# segnalazione_acustico_luminosa.net
KiCad netlist of a schematic drawn in EAGLE
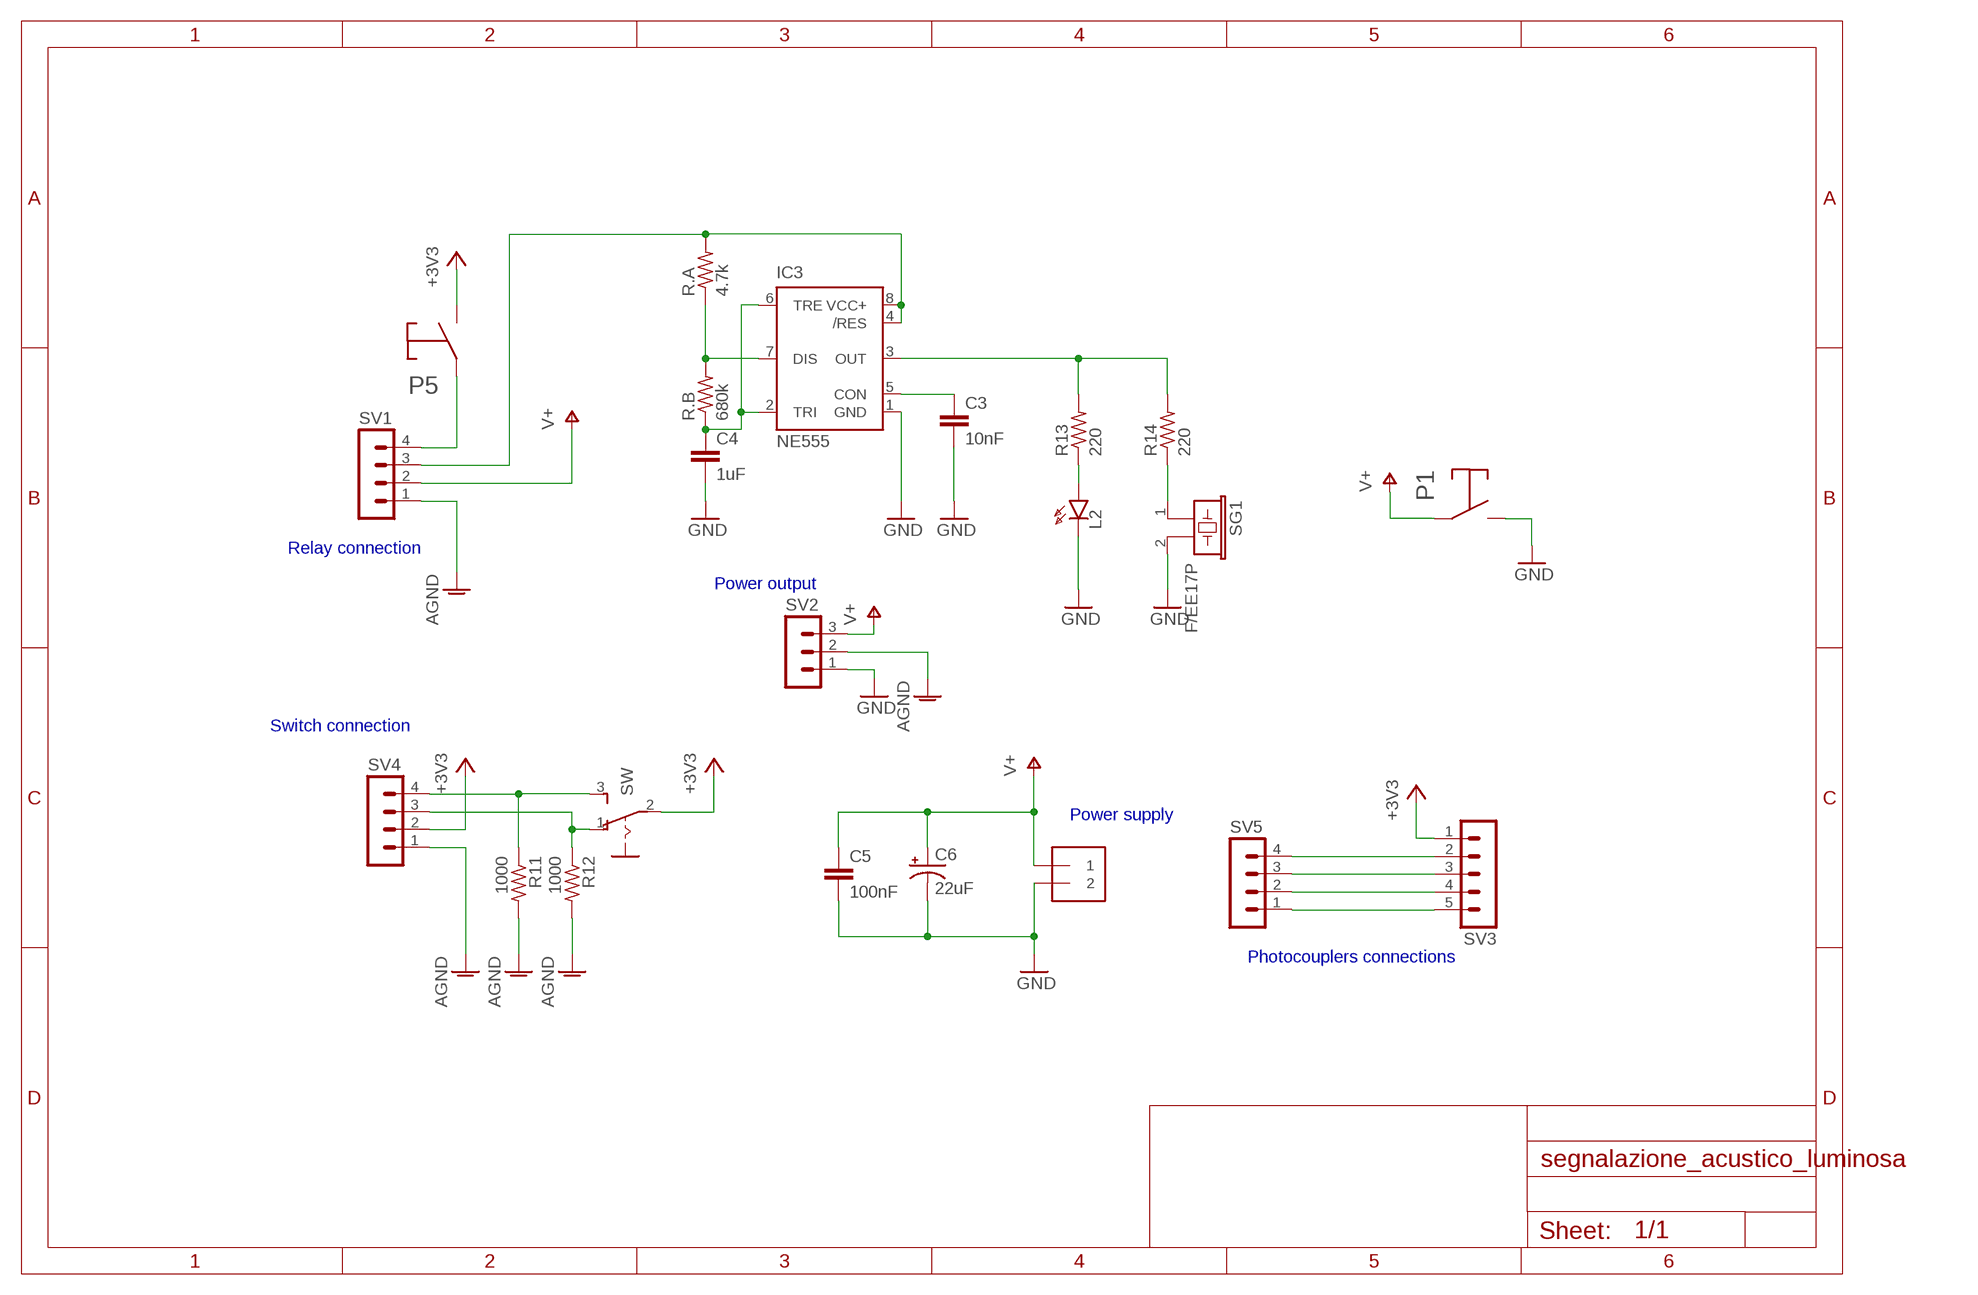
[diagram p0: schematic, sheet 1]

(export (version "E")
  (design (tool "Eeschema 10.0.6"))
  (components
    (comp (ref "C3")
      (value "10nF")
      (footprint "eagle-import:C025-024X044")
      (libsource (lib "eagle-import") (part "C-EU025-024X044"))
    )
    (comp (ref "C4")
      (value "1uF")
      (footprint "eagle-import:C025-024X044")
      (libsource (lib "eagle-import") (part "C-EU025-024X044"))
    )
    (comp (ref "C5")
      (value "100nF")
      (footprint "eagle-import:C025-024X044")
      (libsource (lib "eagle-import") (part "C-EU025-024X044"))
    )
    (comp (ref "C6")
      (value "22uF")
      (footprint "eagle-import:E2,5-6E")
      (libsource (lib "eagle-import") (part "CPOL-USE2,5-6E"))
    )
    (comp (ref "IC3")
      (value "NE555")
      (footprint "eagle-import:DIL-08")
      (fields (field (name "MF") "Arrow Electronics") (field (name "MPN") "NE555N"))
      (libsource (lib "eagle-import") (part "NE555"))
    )
    (comp (ref "J1")
      (value "1X2-3.5MM")
      (footprint "eagle-import:1X2-3.5MM")
      (libsource (lib "eagle-import") (part "1X2-3.5MM"))
    )
    (comp (ref "L2")
      (value "HLMP6")
      (footprint "eagle-import:HLMP6")
      (fields (field (name "MF") "AGILENT TECHNOLOGIES") (field (name "MPN") "HLMP-6500"))
      (libsource (lib "eagle-import") (part "HLMP6"))
    )
    (comp (ref "P1")
      (value "PULS")
      (footprint "eagle-import:2TULIP")
      (libsource (lib "eagle-import") (part "PULS"))
    )
    (comp (ref "P5")
      (value "PULS")
      (footprint "eagle-import:2TULIP")
      (libsource (lib "eagle-import") (part "PULS"))
    )
    (comp (ref "R.A")
      (value "4.7k")
      (footprint "eagle-import:0207_10")
      (libsource (lib "eagle-import") (part "R-US_0207/10"))
    )
    (comp (ref "R.B")
      (value "680k")
      (footprint "eagle-import:0207_10")
      (libsource (lib "eagle-import") (part "R-US_0207/10"))
    )
    (comp (ref "R11")
      (value "1000")
      (footprint "eagle-import:0207_10")
      (libsource (lib "eagle-import") (part "R-US_0207/10"))
    )
    (comp (ref "R12")
      (value "1000")
      (footprint "eagle-import:0207_10")
      (libsource (lib "eagle-import") (part "R-US_0207/10"))
    )
    (comp (ref "R13")
      (value "220")
      (footprint "eagle-import:0207_10")
      (libsource (lib "eagle-import") (part "R-US_0207/10"))
    )
    (comp (ref "R14")
      (value "220")
      (footprint "eagle-import:0207_10")
      (libsource (lib "eagle-import") (part "R-US_0207/10"))
    )
    (comp (ref "SG1")
      (value "F/EE17P")
      (footprint "eagle-import:F_EE17P")
      (libsource (lib "eagle-import") (part "F/EE17P"))
    )
    (comp (ref "SV1")
      (value "MA04-1")
      (footprint "eagle-import:MA04-1")
      (libsource (lib "eagle-import") (part "MA04-1"))
    )
    (comp (ref "SV2")
      (value "MA03-1")
      (footprint "eagle-import:MA03-1")
      (libsource (lib "eagle-import") (part "MA03-1"))
    )
    (comp (ref "SV3")
      (value "MA05-1")
      (footprint "eagle-import:MA05-1")
      (libsource (lib "eagle-import") (part "MA05-1"))
    )
    (comp (ref "SV4")
      (value "MA04-1")
      (footprint "eagle-import:MA04-1")
      (libsource (lib "eagle-import") (part "MA04-1"))
    )
    (comp (ref "SV5")
      (value "MA04-1")
      (footprint "eagle-import:MA04-1")
      (libsource (lib "eagle-import") (part "MA04-1"))
    )
    (comp (ref "SW")
      (value "M251")
      (footprint "eagle-import:M251")
      (libsource (lib "eagle-import") (part "M251"))
    )
  )
  (nets
    (net (code "1") (name "+3V3") (class "Default")
      (node (ref "P5") (pin "1") (pinfunction "P$1_1") (pintype "bidirectional"))
      (node (ref "SV3") (pin "1") (pinfunction "1_1") (pintype "passive"))
      (node (ref "SV4") (pin "2") (pinfunction "2_2") (pintype "passive"))
      (node (ref "SW") (pin "2") (pinfunction "P_2") (pintype "passive"))
    )
    (net (code "2") (name "AGND") (class "Default")
      (node (ref "R11") (pin "2") (pinfunction "2_2") (pintype "passive"))
      (node (ref "R12") (pin "2") (pinfunction "2_2") (pintype "passive"))
      (node (ref "SV1") (pin "1") (pinfunction "1_1") (pintype "passive"))
      (node (ref "SV2") (pin "2") (pinfunction "2_2") (pintype "passive"))
      (node (ref "SV4") (pin "1") (pinfunction "1_1") (pintype "passive"))
    )
    (net (code "3") (name "GND") (class "Default")
      (node (ref "C3") (pin "2") (pinfunction "2_2") (pintype "passive"))
      (node (ref "C4") (pin "2") (pinfunction "2_2") (pintype "passive"))
      (node (ref "C5") (pin "2") (pinfunction "2_2") (pintype "passive"))
      (node (ref "C6") (pin "-") (pinfunction "-_-") (pintype "passive"))
      (node (ref "IC3") (pin "1") (pinfunction "GND_1") (pintype "power_in"))
      (node (ref "J1") (pin "2") (pinfunction "2_2") (pintype "passive"))
      (node (ref "L2") (pin "K") (pinfunction "K_K") (pintype "passive"))
      (node (ref "P1") (pin "1") (pinfunction "P$1_1") (pintype "bidirectional"))
      (node (ref "SG1") (pin "2") (pinfunction "2_2") (pintype "passive"))
      (node (ref "SV2") (pin "1") (pinfunction "1_1") (pintype "passive"))
    )
    (net (code "4") (name "Net-(IC3-CON)") (class "Default")
      (node (ref "C3") (pin "1") (pinfunction "1_1") (pintype "passive"))
      (node (ref "IC3") (pin "5") (pinfunction "CON_5") (pintype "input"))
    )
    (net (code "5") (name "Net-(IC3-DIS)") (class "Default")
      (node (ref "IC3") (pin "7") (pinfunction "DIS_7") (pintype "input"))
      (node (ref "R.A") (pin "1") (pinfunction "1_1") (pintype "passive"))
      (node (ref "R.B") (pin "2") (pinfunction "2_2") (pintype "passive"))
    )
    (net (code "6") (name "Net-(IC3-OUT)") (class "Default")
      (node (ref "IC3") (pin "3") (pinfunction "OUT_3") (pintype "output"))
      (node (ref "R13") (pin "2") (pinfunction "2_2") (pintype "passive"))
      (node (ref "R14") (pin "2") (pinfunction "2_2") (pintype "passive"))
    )
    (net (code "7") (name "Net-(IC3-TRE)") (class "Default")
      (node (ref "C4") (pin "1") (pinfunction "1_1") (pintype "passive"))
      (node (ref "IC3") (pin "2") (pinfunction "TRI_2") (pintype "input"))
      (node (ref "IC3") (pin "6") (pinfunction "TRE_6") (pintype "input"))
      (node (ref "R.B") (pin "1") (pinfunction "1_1") (pintype "passive"))
    )
    (net (code "8") (name "Net-(IC3-VCC+)") (class "Default")
      (node (ref "IC3") (pin "4") (pinfunction "/RES_4") (pintype "input"))
      (node (ref "IC3") (pin "8") (pinfunction "VCC+_8") (pintype "power_in"))
      (node (ref "R.A") (pin "2") (pinfunction "2_2") (pintype "passive"))
      (node (ref "SV1") (pin "3") (pinfunction "3_3") (pintype "passive"))
    )
    (net (code "9") (name "Net-(L2-PadA)") (class "Default")
      (node (ref "L2") (pin "A") (pinfunction "A_A") (pintype "passive"))
      (node (ref "R13") (pin "1") (pinfunction "1_1") (pintype "passive"))
    )
    (net (code "10") (name "Net-(P5-P$2)") (class "Default")
      (node (ref "P5") (pin "2") (pinfunction "P$2_2") (pintype "bidirectional"))
      (node (ref "SV1") (pin "4") (pinfunction "4_4") (pintype "passive"))
    )
    (net (code "11") (name "Net-(R14-Pad1)") (class "Default")
      (node (ref "R14") (pin "1") (pinfunction "1_1") (pintype "passive"))
      (node (ref "SG1") (pin "1") (pinfunction "1_1") (pintype "passive"))
    )
    (net (code "12") (name "Net-(SV3-Pad2)") (class "Default")
      (node (ref "SV3") (pin "2") (pinfunction "2_2") (pintype "passive"))
      (node (ref "SV5") (pin "4") (pinfunction "4_4") (pintype "passive"))
    )
    (net (code "13") (name "Net-(SV3-Pad3)") (class "Default")
      (node (ref "SV3") (pin "3") (pinfunction "3_3") (pintype "passive"))
      (node (ref "SV5") (pin "3") (pinfunction "3_3") (pintype "passive"))
    )
    (net (code "14") (name "Net-(SV3-Pad4)") (class "Default")
      (node (ref "SV3") (pin "4") (pinfunction "4_4") (pintype "passive"))
      (node (ref "SV5") (pin "2") (pinfunction "2_2") (pintype "passive"))
    )
    (net (code "15") (name "Net-(SV3-Pad5)") (class "Default")
      (node (ref "SV3") (pin "5") (pinfunction "5_5") (pintype "passive"))
      (node (ref "SV5") (pin "1") (pinfunction "1_1") (pintype "passive"))
    )
    (net (code "16") (name "Net-(SW-O)") (class "Default")
      (node (ref "R12") (pin "1") (pinfunction "1_1") (pintype "passive"))
      (node (ref "SV4") (pin "3") (pinfunction "3_3") (pintype "passive"))
      (node (ref "SW") (pin "1") (pinfunction "O_1") (pintype "passive"))
    )
    (net (code "17") (name "Net-(SW-S)") (class "Default")
      (node (ref "R11") (pin "1") (pinfunction "1_1") (pintype "passive"))
      (node (ref "SV4") (pin "4") (pinfunction "4_4") (pintype "passive"))
      (node (ref "SW") (pin "3") (pinfunction "S_3") (pintype "passive"))
    )
    (net (code "18") (name "V+") (class "Default")
      (node (ref "C5") (pin "1") (pinfunction "1_1") (pintype "passive"))
      (node (ref "C6") (pin "+") (pinfunction "+_+") (pintype "passive"))
      (node (ref "J1") (pin "1") (pinfunction "1_1") (pintype "passive"))
      (node (ref "P1") (pin "2") (pinfunction "P$2_2") (pintype "bidirectional"))
      (node (ref "SV1") (pin "2") (pinfunction "2_2") (pintype "passive"))
      (node (ref "SV2") (pin "3") (pinfunction "3_3") (pintype "passive"))
    )
  )
)
